# HUD.net
KiCad netlist of a schematic drawn in Altium Designer
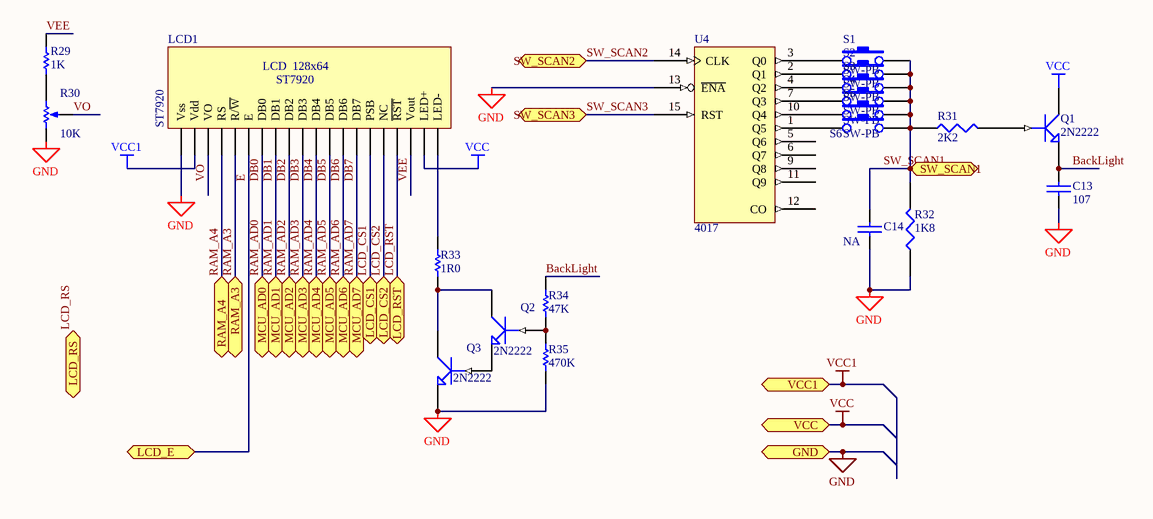
[diagram p0: HUD.SchDoc]

(export (version "E")
  (design (tool "Eeschema 10.0.6"))
  (components
    (comp (ref "C13")
      (value "107")
      (footprint "CAPMP7343X310N")
      (description "Capacitor")
      (libsource (lib "*") (part "CAP"))
    )
    (comp (ref "C14")
      (value "NA")
      (footprint "C6-0805_N")
      (description "Capacitor")
      (libsource (lib "*") (part "CAP"))
    )
    (comp (ref "LCD1")
      (value "ST7920")
      (footprint "LCD12864B")
      (description "ST7920 LCD128X64")
      (libsource (lib "Schlib1") (part "ST7920"))
    )
    (comp (ref "Q1")
      (value "2N2222")
      (footprint "SOT23-3")
      (description "NPN Transistor")
      (libsource (lib "*") (part "NPN1"))
    )
    (comp (ref "Q2")
      (value "2N2222")
      (footprint "SOT23-3")
      (description "NPN Transistor")
      (libsource (lib "*") (part "NPN1"))
    )
    (comp (ref "Q3")
      (value "2N2222")
      (footprint "SOT23-3")
      (description "NPN Transistor")
      (libsource (lib "*") (part "NPN1"))
    )
    (comp (ref "R29")
      (value "1K")
      (footprint "6-0805_N")
      (description "Semiconductor Resistor")
      (fields (field (name "PUBLISHER") "Altium Limited"))
      (libsource (lib "*") (part "Res Semi"))
    )
    (comp (ref "R30")
      (value "10K")
      (footprint "BTXANH")
      (description "Potentiometer")
      (fields (field (name "PUBLISHER") "*"))
      (libsource (lib "*") (part "RPot"))
    )
    (comp (ref "R31") (value "2K2") (footprint "6-0805_N") (libsource (lib "*") (part "RES1")))
    (comp (ref "R32") (value "1K8") (footprint "6-0805_N") (libsource (lib "*") (part "RES1")))
    (comp (ref "R33")
      (value "1R0")
      (footprint "6-0805_N")
      (description "Semiconductor Resistor")
      (fields (field (name "PUBLISHER") "Altium Limited"))
      (libsource (lib "*") (part "Res Semi"))
    )
    (comp (ref "R34")
      (value "47K")
      (footprint "6-0805_N")
      (description "Semiconductor Resistor")
      (fields (field (name "PUBLISHER") "Altium Limited"))
      (libsource (lib "*") (part "Res Semi"))
    )
    (comp (ref "R35")
      (value "470K")
      (footprint "6-0805_N")
      (description "Semiconductor Resistor")
      (fields (field (name "PUBLISHER") "Altium Limited"))
      (libsource (lib "*") (part "Res Semi"))
    )
    (comp (ref "S1") (value "SW-PB") (footprint "CTCHIP_TO") (libsource (lib "*") (part "SW-PB")))
    (comp (ref "S2") (value "SW-PB") (footprint "CTCHIP_TO") (libsource (lib "*") (part "SW-PB")))
    (comp (ref "S3") (value "SW-PB") (footprint "CTCHIP_TO") (libsource (lib "*") (part "SW-PB")))
    (comp (ref "S4") (value "SW-PB") (footprint "CTCHIP_TO") (libsource (lib "*") (part "SW-PB")))
    (comp (ref "S5") (value "SW-PB") (footprint "CTCHIP_TO") (libsource (lib "*") (part "SW-PB")))
    (comp (ref "S6") (value "SW-PB") (footprint "CTCHIP_TO") (libsource (lib "*") (part "SW-PB")))
    (comp (ref "U4") (value "4017") (footprint "SOIC127P600X175-16AN") (libsource (lib "*") (part "4017")))
  )
  (nets
    (net (code "1") (name "/BackLight") (class "Default")
      (node (ref "C13") (pin "1") (pinfunction "1_1") (pintype "passive"))
      (node (ref "Q1") (pin "2") (pinfunction "E_2") (pintype "passive"))
      (node (ref "R34") (pin "2") (pinfunction "2_2") (pintype "passive"))
    )
    (net (code "2") (name "/DB0") (class "Default")
      (node (ref "LCD1") (pin "7") (pinfunction "DB0_7") (pintype "passive"))
    )
    (net (code "3") (name "/DB1") (class "Default")
      (node (ref "LCD1") (pin "8") (pinfunction "DB1_8") (pintype "passive"))
    )
    (net (code "4") (name "/DB2") (class "Default")
      (node (ref "LCD1") (pin "9") (pinfunction "DB2_9") (pintype "passive"))
    )
    (net (code "5") (name "/DB3") (class "Default")
      (node (ref "LCD1") (pin "10") (pinfunction "DB3_10") (pintype "passive"))
    )
    (net (code "6") (name "/DB4") (class "Default")
      (node (ref "LCD1") (pin "11") (pinfunction "DB4_11") (pintype "passive"))
    )
    (net (code "7") (name "/DB5") (class "Default")
      (node (ref "LCD1") (pin "12") (pinfunction "DB5_12") (pintype "passive"))
    )
    (net (code "8") (name "/DB6") (class "Default")
      (node (ref "LCD1") (pin "13") (pinfunction "DB6_13") (pintype "passive"))
    )
    (net (code "9") (name "/DB7") (class "Default")
      (node (ref "LCD1") (pin "14") (pinfunction "DB7_14") (pintype "passive"))
    )
    (net (code "10") (name "/E") (class "Default")
      (node (ref "LCD1") (pin "6") (pinfunction "E_6") (pintype "passive"))
    )
    (net (code "11") (name "/LCD_CS1") (class "Default")
      (node (ref "LCD1") (pin "15") (pinfunction "PSB_15") (pintype "passive"))
    )
    (net (code "12") (name "/LCD_CS2") (class "Default")
      (node (ref "LCD1") (pin "16") (pinfunction "NC_16") (pintype "passive"))
    )
    (net (code "14") (name "/LCD_RST") (class "Default")
      (node (ref "LCD1") (pin "17") (pinfunction "~{RST}_17") (pintype "passive"))
    )
    (net (code "15") (name "/RAM_A3") (class "Default")
      (node (ref "LCD1") (pin "5") (pinfunction "R/~{W}_5") (pintype "passive"))
    )
    (net (code "16") (name "/RAM_A4") (class "Default")
      (node (ref "LCD1") (pin "4") (pinfunction "RS_4") (pintype "passive"))
    )
    (net (code "17") (name "/SW_SCAN1") (class "Default")
      (node (ref "C14") (pin "1") (pinfunction "1_1") (pintype "passive"))
      (node (ref "R31") (pin "1") (pinfunction "1_1") (pintype "passive"))
      (node (ref "R32") (pin "2") (pinfunction "2_2") (pintype "passive"))
      (node (ref "S1") (pin "2") (pinfunction "2_2") (pintype "passive"))
      (node (ref "S2") (pin "2") (pinfunction "2_2") (pintype "passive"))
      (node (ref "S3") (pin "2") (pinfunction "2_2") (pintype "passive"))
      (node (ref "S4") (pin "2") (pinfunction "2_2") (pintype "passive"))
      (node (ref "S5") (pin "2") (pinfunction "2_2") (pintype "passive"))
      (node (ref "S6") (pin "2") (pinfunction "2_2") (pintype "passive"))
    )
    (net (code "18") (name "/SW_SCAN2") (class "Default")
      (node (ref "U4") (pin "14") (pinfunction "CLK_14") (pintype "input"))
    )
    (net (code "19") (name "/SW_SCAN3") (class "Default")
      (node (ref "U4") (pin "15") (pinfunction "RST_15") (pintype "input"))
    )
    (net (code "20") (name "/VEE") (class "Default")
      (node (ref "LCD1") (pin "18") (pinfunction "Vout_18") (pintype "passive"))
      (node (ref "R29") (pin "2") (pinfunction "2_2") (pintype "passive"))
    )
    (net (code "21") (name "/VO") (class "Default")
      (node (ref "LCD1") (pin "3") (pinfunction "VO_3") (pintype "passive"))
      (node (ref "R30") (pin "2") (pinfunction "TAP_2") (pintype "passive"))
    )
    (net (code "22") (name "GND") (class "Default")
      (node (ref "C13") (pin "2") (pinfunction "2_2") (pintype "passive"))
      (node (ref "C14") (pin "2") (pinfunction "2_2") (pintype "passive"))
      (node (ref "LCD1") (pin "1") (pinfunction "Vss_1") (pintype "passive"))
      (node (ref "Q3") (pin "2") (pinfunction "E_2") (pintype "passive"))
      (node (ref "R30") (pin "1") (pinfunction "TOP_1") (pintype "passive"))
      (node (ref "R32") (pin "1") (pinfunction "1_1") (pintype "passive"))
      (node (ref "R35") (pin "1") (pinfunction "1_1") (pintype "passive"))
      (node (ref "U4") (pin "13") (pinfunction "~{ENA}_13") (pintype "input"))
      (node (ref "U4") (pin "8") (pinfunction "GND_8") (pintype "power_in"))
    )
    (net (code "23") (name "Net-(LCD1-LED-)") (class "Default")
      (node (ref "LCD1") (pin "20") (pinfunction "LED-_20") (pintype "passive"))
      (node (ref "R33") (pin "2") (pinfunction "2_2") (pintype "passive"))
    )
    (net (code "24") (name "Net-(Q1-B)") (class "Default")
      (node (ref "Q1") (pin "1") (pinfunction "B_1") (pintype "input"))
      (node (ref "R31") (pin "2") (pinfunction "2_2") (pintype "passive"))
    )
    (net (code "25") (name "Net-(Q2-B)") (class "Default")
      (node (ref "Q2") (pin "1") (pinfunction "B_1") (pintype "input"))
      (node (ref "R34") (pin "1") (pinfunction "1_1") (pintype "passive"))
      (node (ref "R35") (pin "2") (pinfunction "2_2") (pintype "passive"))
    )
    (net (code "26") (name "Net-(Q2-C)") (class "Default")
      (node (ref "Q2") (pin "3") (pinfunction "C_3") (pintype "passive"))
      (node (ref "Q3") (pin "3") (pinfunction "C_3") (pintype "passive"))
      (node (ref "R33") (pin "1") (pinfunction "1_1") (pintype "passive"))
    )
    (net (code "27") (name "Net-(Q2-E)") (class "Default")
      (node (ref "Q2") (pin "2") (pinfunction "E_2") (pintype "passive"))
      (node (ref "Q3") (pin "1") (pinfunction "B_1") (pintype "input"))
    )
    (net (code "28") (name "Net-(R30-BOT)") (class "Default")
      (node (ref "R29") (pin "1") (pinfunction "1_1") (pintype "passive"))
      (node (ref "R30") (pin "3") (pinfunction "BOT_3") (pintype "passive"))
    )
    (net (code "29") (name "Net-(U4-Q0)") (class "Default")
      (node (ref "S1") (pin "1") (pinfunction "1_1") (pintype "passive"))
      (node (ref "U4") (pin "3") (pinfunction "Q0_3") (pintype "output"))
    )
    (net (code "30") (name "Net-(U4-Q1)") (class "Default")
      (node (ref "S2") (pin "1") (pinfunction "1_1") (pintype "passive"))
      (node (ref "U4") (pin "2") (pinfunction "Q1_2") (pintype "output"))
    )
    (net (code "31") (name "Net-(U4-Q2)") (class "Default")
      (node (ref "S3") (pin "1") (pinfunction "1_1") (pintype "passive"))
      (node (ref "U4") (pin "4") (pinfunction "Q2_4") (pintype "output"))
    )
    (net (code "32") (name "Net-(U4-Q3)") (class "Default")
      (node (ref "S4") (pin "1") (pinfunction "1_1") (pintype "passive"))
      (node (ref "U4") (pin "7") (pinfunction "Q3_7") (pintype "output"))
    )
    (net (code "33") (name "Net-(U4-Q4)") (class "Default")
      (node (ref "S5") (pin "1") (pinfunction "1_1") (pintype "passive"))
      (node (ref "U4") (pin "10") (pinfunction "Q4_10") (pintype "output"))
    )
    (net (code "34") (name "Net-(U4-Q5)") (class "Default")
      (node (ref "S6") (pin "1") (pinfunction "1_1") (pintype "passive"))
      (node (ref "U4") (pin "1") (pinfunction "Q5_1") (pintype "output"))
    )
    (net (code "35") (name "VCC") (class "Default")
      (node (ref "LCD1") (pin "19") (pinfunction "LED+_19") (pintype "passive"))
      (node (ref "Q1") (pin "3") (pinfunction "C_3") (pintype "passive"))
      (node (ref "U4") (pin "16") (pinfunction "VCC_16") (pintype "power_in"))
    )
    (net (code "36") (name "VCC1") (class "Default")
      (node (ref "LCD1") (pin "2") (pinfunction "Vdd_2") (pintype "passive"))
    )
    (net (code "37") (name "unconnected-(U4-CO-Pad12)") (class "Default")
      (node (ref "U4") (pin "12") (pinfunction "CO_12") (pintype "output"))
    )
    (net (code "38") (name "unconnected-(U4-Q6-Pad5)") (class "Default")
      (node (ref "U4") (pin "5") (pinfunction "Q6_5") (pintype "output"))
    )
    (net (code "39") (name "unconnected-(U4-Q7-Pad6)") (class "Default")
      (node (ref "U4") (pin "6") (pinfunction "Q7_6") (pintype "output"))
    )
    (net (code "40") (name "unconnected-(U4-Q8-Pad9)") (class "Default")
      (node (ref "U4") (pin "9") (pinfunction "Q8_9") (pintype "output"))
    )
    (net (code "41") (name "unconnected-(U4-Q9-Pad11)") (class "Default")
      (node (ref "U4") (pin "11") (pinfunction "Q9_11") (pintype "output"))
    )
  )
)
